# rhome_3.net
KiCad netlist of a schematic drawn in EAGLE
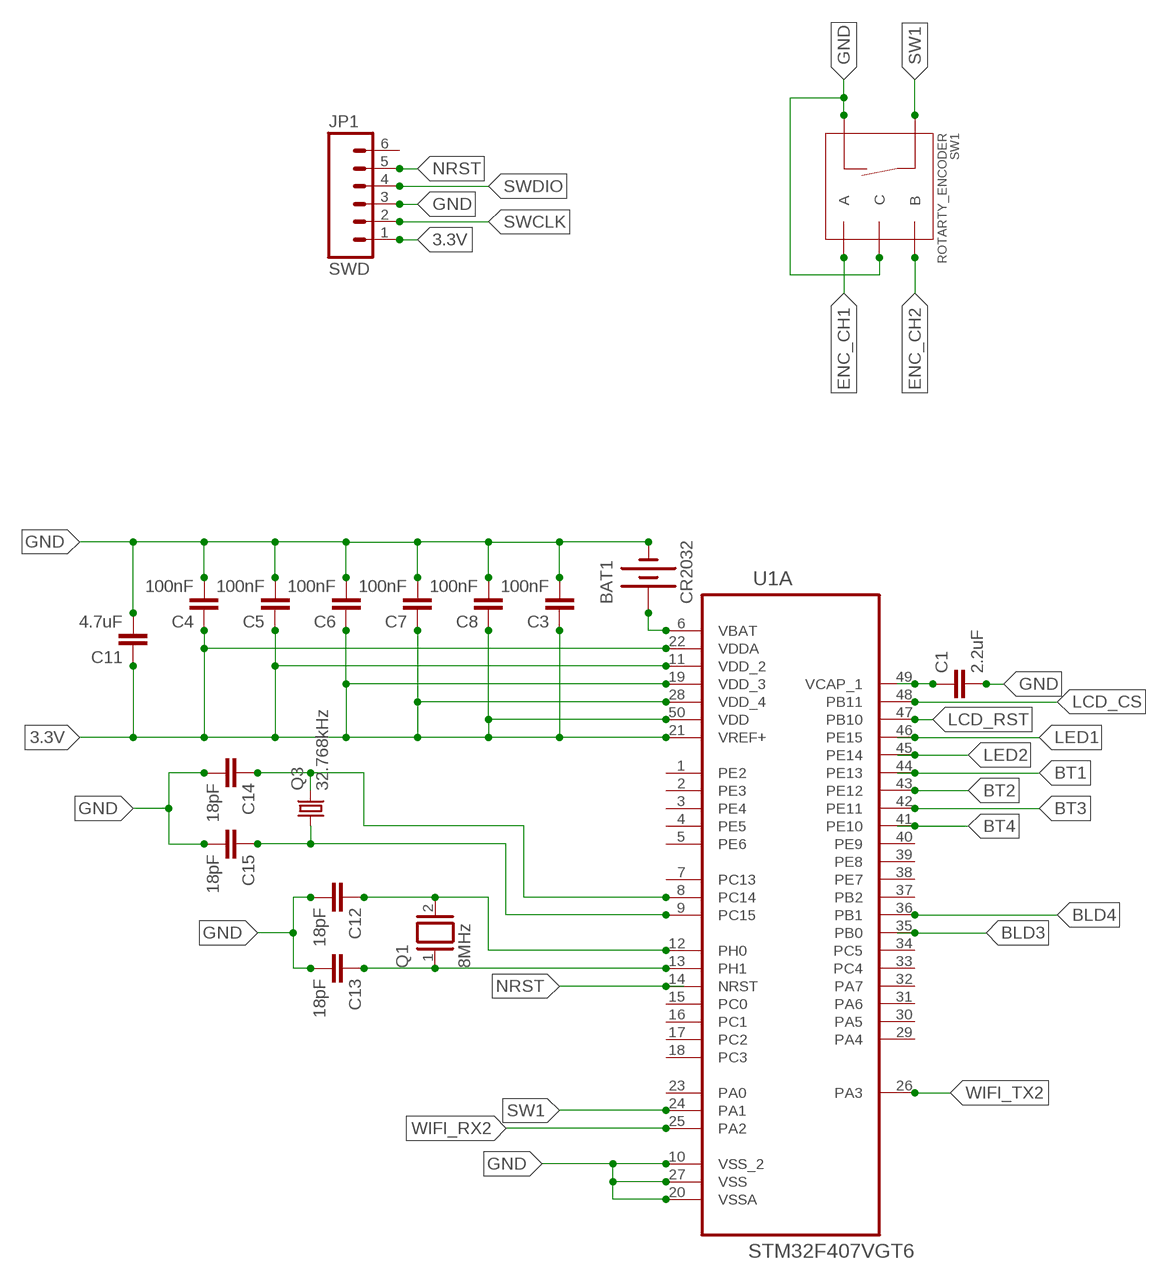
[diagram p0: schematic, sheet 1, part 1 of 2]
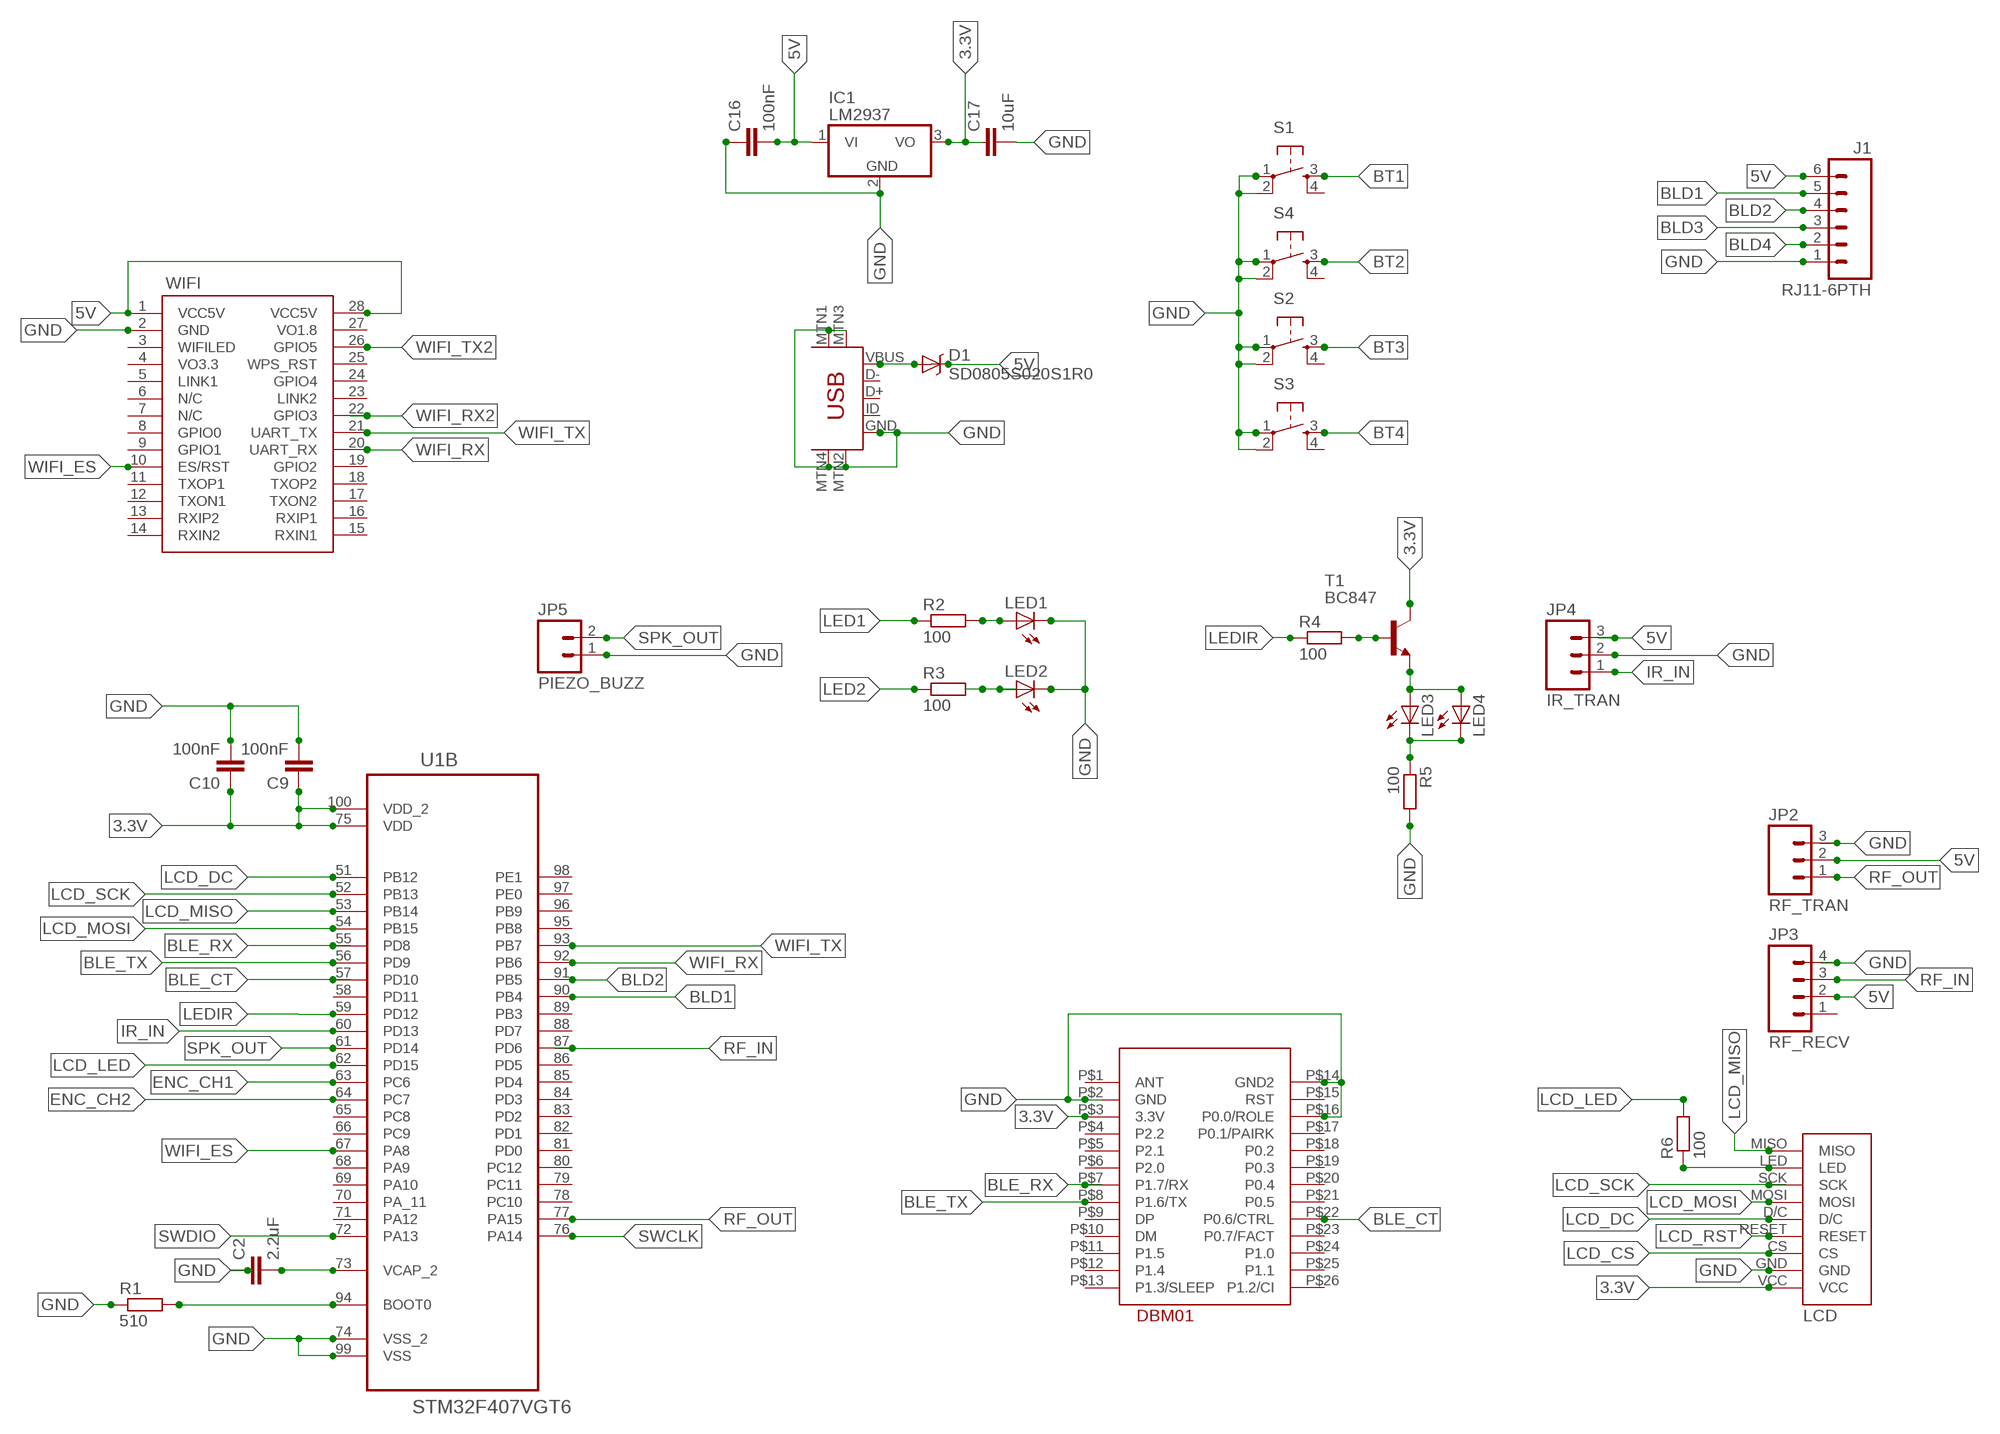
[diagram p1: schematic, sheet 1, part 2 of 2]

(export (version "E")
  (design (tool "Eeschema 10.0.6"))
  (components
    (comp (ref "BAT1")
      (value "CR2032")
      (footprint "eagle-import:BATTCON_20MM")
      (libsource (lib "eagle-import") (part "BATTERY20SMD"))
    )
    (comp (ref "C1")
      (value "2.2uF")
      (footprint "eagle-import:0805")
      (libsource (lib "eagle-import") (part "CAP0805"))
    )
    (comp (ref "C2")
      (value "2.2uF")
      (footprint "eagle-import:0805")
      (libsource (lib "eagle-import") (part "CAP0805"))
    )
    (comp (ref "C3")
      (value "100nF")
      (footprint "eagle-import:0805")
      (libsource (lib "eagle-import") (part "CAP0805"))
    )
    (comp (ref "C4")
      (value "100nF")
      (footprint "eagle-import:0805")
      (libsource (lib "eagle-import") (part "CAP0805"))
    )
    (comp (ref "C5")
      (value "100nF")
      (footprint "eagle-import:0805")
      (libsource (lib "eagle-import") (part "CAP0805"))
    )
    (comp (ref "C6")
      (value "100nF")
      (footprint "eagle-import:0805")
      (libsource (lib "eagle-import") (part "CAP0805"))
    )
    (comp (ref "C7")
      (value "100nF")
      (footprint "eagle-import:0805")
      (libsource (lib "eagle-import") (part "CAP0805"))
    )
    (comp (ref "C8")
      (value "100nF")
      (footprint "eagle-import:0805")
      (libsource (lib "eagle-import") (part "CAP0805"))
    )
    (comp (ref "C9")
      (value "100nF")
      (footprint "eagle-import:0805")
      (libsource (lib "eagle-import") (part "CAP0805"))
    )
    (comp (ref "C10")
      (value "100nF")
      (footprint "eagle-import:0805")
      (libsource (lib "eagle-import") (part "CAP0805"))
    )
    (comp (ref "C11")
      (value "4.7uF")
      (footprint "eagle-import:0805")
      (libsource (lib "eagle-import") (part "CAP0805"))
    )
    (comp (ref "C12")
      (value "18pF")
      (footprint "eagle-import:0805")
      (libsource (lib "eagle-import") (part "CAP0805"))
    )
    (comp (ref "C13")
      (value "18pF")
      (footprint "eagle-import:0805")
      (libsource (lib "eagle-import") (part "CAP0805"))
    )
    (comp (ref "C14")
      (value "18pF")
      (footprint "eagle-import:0805")
      (libsource (lib "eagle-import") (part "CAP0805"))
    )
    (comp (ref "C15")
      (value "18pF")
      (footprint "eagle-import:0805")
      (libsource (lib "eagle-import") (part "CAP0805"))
    )
    (comp (ref "C16")
      (value "100nF")
      (footprint "eagle-import:0805")
      (libsource (lib "eagle-import") (part "CAP0805"))
    )
    (comp (ref "C17")
      (value "10uF")
      (footprint "eagle-import:0805")
      (libsource (lib "eagle-import") (part "CAP0805"))
    )
    (comp (ref "D1")
      (value "SD0805S020S1R0")
      (footprint "eagle-import:SOD-323")
      (libsource (lib "eagle-import") (part "BAT20JFILM"))
    )
    (comp (ref "DBM01")
      (value "DBM01")
      (footprint "eagle-import:SMD")
      (libsource (lib "eagle-import") (part "DBM01"))
    )
    (comp (ref "IC1")
      (value "LM2937")
      (footprint "eagle-import:TO263-3")
      (libsource (lib "eagle-import") (part "LM2937"))
    )
    (comp (ref "J1")
      (value "RJ11-6PTH")
      (footprint "eagle-import:RJ11-6")
      (libsource (lib "eagle-import") (part "RJ11-6PTH"))
    )
    (comp (ref "JP1")
      (value "SWD")
      (footprint "eagle-import:1X06")
      (libsource (lib "eagle-import") (part "M06SIP"))
    )
    (comp (ref "JP2")
      (value "RF_TRAN")
      (footprint "eagle-import:1X03")
      (libsource (lib "eagle-import") (part "M03PTH"))
    )
    (comp (ref "JP3")
      (value "RF_RECV")
      (footprint "eagle-import:1X04")
      (libsource (lib "eagle-import") (part "M04PTH"))
    )
    (comp (ref "JP4")
      (value "IR_TRAN")
      (footprint "eagle-import:1X03")
      (libsource (lib "eagle-import") (part "M03PTH"))
    )
    (comp (ref "JP5")
      (value "PIEZO_BUZZ")
      (footprint "eagle-import:1X02_LOCK")
      (libsource (lib "eagle-import") (part "M02LOCK"))
    )
    (comp (ref "LCD")
      (value "ILI9341_SPI_LCD")
      (footprint "eagle-import:LCD")
      (libsource (lib "eagle-import") (part "ILI9341_SPI_LCD"))
    )
    (comp (ref "LED1")
      (value "LED5MM")
      (footprint "eagle-import:LED5MM")
      (libsource (lib "eagle-import") (part "LED5MM"))
    )
    (comp (ref "LED2")
      (value "LED5MM")
      (footprint "eagle-import:LED5MM")
      (libsource (lib "eagle-import") (part "LED5MM"))
    )
    (comp (ref "LED3")
      (value "LED5MM")
      (footprint "eagle-import:LED5MM")
      (libsource (lib "eagle-import") (part "LED5MM"))
    )
    (comp (ref "LED4")
      (value "LED5MM")
      (footprint "eagle-import:LED5MM")
      (libsource (lib "eagle-import") (part "LED5MM"))
    )
    (comp (ref "Q1")
      (value "8MHz")
      (footprint "eagle-import:QS")
      (libsource (lib "eagle-import") (part "XTAL/S"))
    )
    (comp (ref "Q3")
      (value "32.768kHz")
      (footprint "eagle-import:MC-306")
      (fields (field (name "MPN") "MC-306 60.0KHZ  100PPM ,12.5PF"))
      (libsource (lib "eagle-import") (part "MC-306"))
    )
    (comp (ref "R1")
      (value "510")
      (footprint "eagle-import:R0805")
      (libsource (lib "eagle-import") (part "R-EU_R0805"))
    )
    (comp (ref "R2")
      (value "100")
      (footprint "eagle-import:R0805")
      (libsource (lib "eagle-import") (part "R-EU_R0805"))
    )
    (comp (ref "R3")
      (value "100")
      (footprint "eagle-import:R0805")
      (libsource (lib "eagle-import") (part "R-EU_R0805"))
    )
    (comp (ref "R4")
      (value "100")
      (footprint "eagle-import:R0805")
      (libsource (lib "eagle-import") (part "R-EU_R0805"))
    )
    (comp (ref "R5")
      (value "100")
      (footprint "eagle-import:R0805")
      (libsource (lib "eagle-import") (part "R-EU_R0805"))
    )
    (comp (ref "R6")
      (value "100")
      (footprint "eagle-import:R0805")
      (libsource (lib "eagle-import") (part "R-EU_R0805"))
    )
    (comp (ref "S1")
      (value "TAC_SWITCHPTH")
      (footprint "eagle-import:TACTILE-PTH")
      (libsource (lib "eagle-import") (part "TAC_SWITCHPTH"))
    )
    (comp (ref "S2")
      (value "TAC_SWITCHPTH")
      (footprint "eagle-import:TACTILE-PTH")
      (libsource (lib "eagle-import") (part "TAC_SWITCHPTH"))
    )
    (comp (ref "S3")
      (value "TAC_SWITCHPTH")
      (footprint "eagle-import:TACTILE-PTH")
      (libsource (lib "eagle-import") (part "TAC_SWITCHPTH"))
    )
    (comp (ref "S4")
      (value "TAC_SWITCHPTH")
      (footprint "eagle-import:TACTILE-PTH")
      (libsource (lib "eagle-import") (part "TAC_SWITCHPTH"))
    )
    (comp (ref "SW1")
      (value "ROTARTY_ENCODER")
      (footprint "eagle-import:ROTARY_ENC_PLAIN")
      (libsource (lib "eagle-import") (part "ROTARTY_ENCODER"))
    )
    (comp (ref "T1")
      (value "BC847")
      (footprint "eagle-import:SOT23")
      (libsource (lib "eagle-import") (part "BC847"))
    )
    (comp (ref "U$1")
      (value "USB-MINIB-5PIN")
      (footprint "eagle-import:USB-MINIB")
      (libsource (lib "eagle-import") (part "USB-MINIB-5PIN"))
    )
    (comp (ref "U1")
      (value "STM32F407VGT6")
      (footprint "eagle-import:QFP50P1600X1600X160-100N")
      (libsource (lib "eagle-import") (part "STM32F407VGT6"))
    )
    (comp (ref "WIFI")
      (value "HLK-RM04")
      (footprint "eagle-import:HLK-RM04")
      (libsource (lib "eagle-import") (part "HLK-RM04"))
    )
  )
  (nets
    (net (code "1") (name "3.3V") (class "Default")
      (node (ref "C10") (pin "1") (pinfunction "1_1") (pintype "passive"))
      (node (ref "C11") (pin "1") (pinfunction "1_1") (pintype "passive"))
      (node (ref "C17") (pin "1") (pinfunction "1_1") (pintype "passive"))
      (node (ref "C3") (pin "1") (pinfunction "1_1") (pintype "passive"))
      (node (ref "C4") (pin "1") (pinfunction "1_1") (pintype "passive"))
      (node (ref "C5") (pin "1") (pinfunction "1_1") (pintype "passive"))
      (node (ref "C6") (pin "1") (pinfunction "1_1") (pintype "passive"))
      (node (ref "C7") (pin "1") (pinfunction "1_1") (pintype "passive"))
      (node (ref "C8") (pin "1") (pinfunction "1_1") (pintype "passive"))
      (node (ref "C9") (pin "1") (pinfunction "1_1") (pintype "passive"))
      (node (ref "DBM01") (pin "P$3") (pinfunction "3.3V_P$3") (pintype "bidirectional"))
      (node (ref "IC1") (pin "3") (pinfunction "VO_3") (pintype "passive"))
      (node (ref "JP1") (pin "1") (pinfunction "1_1") (pintype "passive"))
      (node (ref "LCD") (pin "VCC") (pinfunction "VCC_VCC") (pintype "bidirectional"))
      (node (ref "T1") (pin "3") (pinfunction "C_3") (pintype "passive"))
      (node (ref "U1") (pin "100") (pinfunction "VDD_2_100") (pintype "power_in"))
      (node (ref "U1") (pin "11") (pinfunction "VDD_2_11") (pintype "power_in"))
      (node (ref "U1") (pin "19") (pinfunction "VDD_3_19") (pintype "power_in"))
      (node (ref "U1") (pin "21") (pinfunction "VREF+_21") (pintype "power_in"))
      (node (ref "U1") (pin "22") (pinfunction "VDDA_22") (pintype "power_in"))
      (node (ref "U1") (pin "28") (pinfunction "VDD_4_28") (pintype "power_in"))
      (node (ref "U1") (pin "50") (pinfunction "VDD_50") (pintype "power_in"))
      (node (ref "U1") (pin "75") (pinfunction "VDD_75") (pintype "power_in"))
    )
    (net (code "2") (name "5V") (class "Default")
      (node (ref "C16") (pin "2") (pinfunction "2_2") (pintype "passive"))
      (node (ref "D1") (pin "1") (pinfunction "C_1") (pintype "passive"))
      (node (ref "IC1") (pin "1") (pinfunction "VI_1") (pintype "input"))
      (node (ref "J1") (pin "6") (pinfunction "6_6") (pintype "passive"))
      (node (ref "JP2") (pin "2") (pinfunction "2_2") (pintype "passive"))
      (node (ref "JP3") (pin "2") (pinfunction "2_2") (pintype "passive"))
      (node (ref "JP4") (pin "3") (pinfunction "3_3") (pintype "passive"))
      (node (ref "WIFI") (pin "1") (pinfunction "VCC5V_1") (pintype "bidirectional"))
      (node (ref "WIFI") (pin "28") (pinfunction "VCC5V_28") (pintype "bidirectional"))
    )
    (net (code "3") (name "BLD1") (class "Default")
      (node (ref "J1") (pin "5") (pinfunction "5_5") (pintype "passive"))
      (node (ref "U1") (pin "90") (pinfunction "PB4_90") (pintype "bidirectional"))
    )
    (net (code "4") (name "BLD2") (class "Default")
      (node (ref "J1") (pin "4") (pinfunction "4_4") (pintype "passive"))
      (node (ref "U1") (pin "91") (pinfunction "PB5_91") (pintype "bidirectional"))
    )
    (net (code "5") (name "BLD3") (class "Default")
      (node (ref "J1") (pin "3") (pinfunction "3_3") (pintype "passive"))
      (node (ref "U1") (pin "35") (pinfunction "PB0_35") (pintype "bidirectional"))
    )
    (net (code "6") (name "BLD4") (class "Default")
      (node (ref "J1") (pin "2") (pinfunction "2_2") (pintype "passive"))
      (node (ref "U1") (pin "36") (pinfunction "PB1_36") (pintype "bidirectional"))
    )
    (net (code "7") (name "BLE_CT") (class "Default")
      (node (ref "DBM01") (pin "P$22") (pinfunction "P0.6/CTRL_P$22") (pintype "bidirectional"))
      (node (ref "U1") (pin "57") (pinfunction "PD10_57") (pintype "bidirectional"))
    )
    (net (code "8") (name "BLE_RX") (class "Default")
      (node (ref "DBM01") (pin "P$7") (pinfunction "P1.7/RX_P$7") (pintype "bidirectional"))
      (node (ref "U1") (pin "55") (pinfunction "PD8_55") (pintype "bidirectional"))
    )
    (net (code "9") (name "BLE_TX") (class "Default")
      (node (ref "DBM01") (pin "P$8") (pinfunction "P1.6/TX_P$8") (pintype "bidirectional"))
      (node (ref "U1") (pin "56") (pinfunction "PD9_56") (pintype "bidirectional"))
    )
    (net (code "10") (name "BT1") (class "Default")
      (node (ref "S1") (pin "3") (pinfunction "3_3") (pintype "passive"))
      (node (ref "U1") (pin "44") (pinfunction "PE13_44") (pintype "bidirectional"))
    )
    (net (code "11") (name "BT2") (class "Default")
      (node (ref "S4") (pin "3") (pinfunction "3_3") (pintype "passive"))
      (node (ref "U1") (pin "43") (pinfunction "PE12_43") (pintype "bidirectional"))
    )
    (net (code "12") (name "BT3") (class "Default")
      (node (ref "S2") (pin "3") (pinfunction "3_3") (pintype "passive"))
      (node (ref "U1") (pin "42") (pinfunction "PE11_42") (pintype "bidirectional"))
    )
    (net (code "13") (name "BT4") (class "Default")
      (node (ref "S3") (pin "3") (pinfunction "3_3") (pintype "passive"))
      (node (ref "U1") (pin "41") (pinfunction "PE10_41") (pintype "bidirectional"))
    )
    (net (code "14") (name "ENC_CH1") (class "Default")
      (node (ref "SW1") (pin "A") (pinfunction "A_A") (pintype "bidirectional"))
      (node (ref "U1") (pin "63") (pinfunction "PC6_63") (pintype "bidirectional"))
    )
    (net (code "15") (name "ENC_CH2") (class "Default")
      (node (ref "SW1") (pin "B") (pinfunction "B_B") (pintype "bidirectional"))
      (node (ref "U1") (pin "64") (pinfunction "PC7_64") (pintype "bidirectional"))
    )
    (net (code "16") (name "GND") (class "Default")
      (node (ref "BAT1") (pin "2") (pinfunction "-_2") (pintype "power_in"))
      (node (ref "C1") (pin "2") (pinfunction "2_2") (pintype "passive"))
      (node (ref "C10") (pin "2") (pinfunction "2_2") (pintype "passive"))
      (node (ref "C11") (pin "2") (pinfunction "2_2") (pintype "passive"))
      (node (ref "C12") (pin "2") (pinfunction "2_2") (pintype "passive"))
      (node (ref "C13") (pin "2") (pinfunction "2_2") (pintype "passive"))
      (node (ref "C14") (pin "2") (pinfunction "2_2") (pintype "passive"))
      (node (ref "C15") (pin "2") (pinfunction "2_2") (pintype "passive"))
      (node (ref "C16") (pin "1") (pinfunction "1_1") (pintype "passive"))
      (node (ref "C17") (pin "2") (pinfunction "2_2") (pintype "passive"))
      (node (ref "C2") (pin "1") (pinfunction "1_1") (pintype "passive"))
      (node (ref "C3") (pin "2") (pinfunction "2_2") (pintype "passive"))
      (node (ref "C4") (pin "2") (pinfunction "2_2") (pintype "passive"))
      (node (ref "C5") (pin "2") (pinfunction "2_2") (pintype "passive"))
      (node (ref "C6") (pin "2") (pinfunction "2_2") (pintype "passive"))
      (node (ref "C7") (pin "2") (pinfunction "2_2") (pintype "passive"))
      (node (ref "C8") (pin "2") (pinfunction "2_2") (pintype "passive"))
      (node (ref "C9") (pin "2") (pinfunction "2_2") (pintype "passive"))
      (node (ref "DBM01") (pin "P$14") (pinfunction "GND2_P$14") (pintype "bidirectional"))
      (node (ref "DBM01") (pin "P$16") (pinfunction "P0.0/ROLE_P$16") (pintype "bidirectional"))
      (node (ref "DBM01") (pin "P$2") (pinfunction "GND_P$2") (pintype "bidirectional"))
      (node (ref "IC1") (pin "2") (pinfunction "GND_2") (pintype "passive"))
      (node (ref "J1") (pin "1") (pinfunction "1_1") (pintype "passive"))
      (node (ref "JP1") (pin "3") (pinfunction "3_3") (pintype "passive"))
      (node (ref "JP2") (pin "3") (pinfunction "3_3") (pintype "passive"))
      (node (ref "JP3") (pin "4") (pinfunction "4_4") (pintype "passive"))
      (node (ref "JP4") (pin "2") (pinfunction "2_2") (pintype "passive"))
      (node (ref "JP5") (pin "1") (pinfunction "1_1") (pintype "passive"))
      (node (ref "LCD") (pin "GND") (pinfunction "GND_GND") (pintype "bidirectional"))
      (node (ref "LED1") (pin "K") (pinfunction "C_K") (pintype "passive"))
      (node (ref "LED2") (pin "K") (pinfunction "C_K") (pintype "passive"))
      (node (ref "R1") (pin "1") (pinfunction "1_1") (pintype "passive"))
      (node (ref "R5") (pin "2") (pinfunction "2_2") (pintype "passive"))
      (node (ref "S1") (pin "1") (pinfunction "1_1") (pintype "passive"))
      (node (ref "S1") (pin "2") (pinfunction "2_2") (pintype "passive"))
      (node (ref "S2") (pin "1") (pinfunction "1_1") (pintype "passive"))
      (node (ref "S2") (pin "2") (pinfunction "2_2") (pintype "passive"))
      (node (ref "S3") (pin "1") (pinfunction "1_1") (pintype "passive"))
      (node (ref "S3") (pin "2") (pinfunction "2_2") (pintype "passive"))
      (node (ref "S4") (pin "1") (pinfunction "1_1") (pintype "passive"))
      (node (ref "S4") (pin "2") (pinfunction "2_2") (pintype "passive"))
      (node (ref "SW1") (pin "C") (pinfunction "C_C") (pintype "bidirectional"))
      (node (ref "SW1") (pin "SW-") (pinfunction "SW-_SW-") (pintype "bidirectional"))
      (node (ref "U$1") (pin "GND") (pinfunction "GND_GND") (pintype "bidirectional"))
      (node (ref "U$1") (pin "MTN1") (pinfunction "MTN2_MTN1") (pintype "bidirectional"))
      (node (ref "U$1") (pin "MTN2") (pinfunction "MTN3_MTN2") (pintype "bidirectional"))
      (node (ref "U$1") (pin "MTN3") (pinfunction "MTN1_MTN3") (pintype "bidirectional"))
      (node (ref "U$1") (pin "MTN4") (pinfunction "MTN4_MTN4") (pintype "bidirectional"))
      (node (ref "U1") (pin "10") (pinfunction "VSS_2_10") (pintype "passive"))
      (node (ref "U1") (pin "20") (pinfunction "VSSA_20") (pintype "passive"))
      (node (ref "U1") (pin "27") (pinfunction "VSS_27") (pintype "passive"))
      (node (ref "U1") (pin "74") (pinfunction "VSS_2_74") (pintype "passive"))
      (node (ref "U1") (pin "99") (pinfunction "VSS_99") (pintype "passive"))
      (node (ref "WIFI") (pin "2") (pinfunction "GND_2") (pintype "bidirectional"))
    )
    (net (code "17") (name "IR_IN") (class "Default")
      (node (ref "JP4") (pin "1") (pinfunction "1_1") (pintype "passive"))
      (node (ref "U1") (pin "60") (pinfunction "PD13_60") (pintype "bidirectional"))
    )
    (net (code "18") (name "LCD_CS") (class "Default")
      (node (ref "LCD") (pin "CS") (pinfunction "CS_CS") (pintype "bidirectional"))
      (node (ref "U1") (pin "48") (pinfunction "PB11_48") (pintype "bidirectional"))
    )
    (net (code "19") (name "LCD_DC") (class "Default")
      (node (ref "LCD") (pin "D/C") (pinfunction "D/C_D/C") (pintype "bidirectional"))
      (node (ref "U1") (pin "51") (pinfunction "PB12_51") (pintype "bidirectional"))
    )
    (net (code "20") (name "LCD_LED") (class "Default")
      (node (ref "R6") (pin "2") (pinfunction "2_2") (pintype "passive"))
      (node (ref "U1") (pin "62") (pinfunction "PD15_62") (pintype "bidirectional"))
    )
    (net (code "21") (name "LCD_MISO") (class "Default")
      (node (ref "LCD") (pin "MISO") (pinfunction "MISO_MISO") (pintype "bidirectional"))
      (node (ref "U1") (pin "53") (pinfunction "PB14_53") (pintype "bidirectional"))
    )
    (net (code "22") (name "LCD_MOSI") (class "Default")
      (node (ref "LCD") (pin "MOSI") (pinfunction "MOSI_MOSI") (pintype "bidirectional"))
      (node (ref "U1") (pin "54") (pinfunction "PB15_54") (pintype "bidirectional"))
    )
    (net (code "23") (name "LCD_RST") (class "Default")
      (node (ref "LCD") (pin "RESET") (pinfunction "RESET_RESET") (pintype "bidirectional"))
      (node (ref "U1") (pin "47") (pinfunction "PB10_47") (pintype "bidirectional"))
    )
    (net (code "24") (name "LCD_SCK") (class "Default")
      (node (ref "LCD") (pin "SCK") (pinfunction "SCK_SCK") (pintype "bidirectional"))
      (node (ref "U1") (pin "52") (pinfunction "PB13_52") (pintype "bidirectional"))
    )
    (net (code "25") (name "LED1") (class "Default")
      (node (ref "R2") (pin "1") (pinfunction "1_1") (pintype "passive"))
      (node (ref "U1") (pin "46") (pinfunction "PE15_46") (pintype "bidirectional"))
    )
    (net (code "26") (name "LED2") (class "Default")
      (node (ref "R3") (pin "1") (pinfunction "1_1") (pintype "passive"))
      (node (ref "U1") (pin "45") (pinfunction "PE14_45") (pintype "bidirectional"))
    )
    (net (code "27") (name "LEDIR") (class "Default")
      (node (ref "R4") (pin "1") (pinfunction "1_1") (pintype "passive"))
      (node (ref "U1") (pin "59") (pinfunction "PD12_59") (pintype "bidirectional"))
    )
    (net (code "28") (name "NRST") (class "Default")
      (node (ref "JP1") (pin "5") (pinfunction "5_5") (pintype "passive"))
      (node (ref "U1") (pin "14") (pinfunction "NRST_14") (pintype "bidirectional"))
    )
    (net (code "29") (name "Net-(BAT1-+)") (class "Default")
      (node (ref "BAT1") (pin "1") (pinfunction "+_1") (pintype "power_in"))
      (node (ref "U1") (pin "6") (pinfunction "VBAT_6") (pintype "power_in"))
    )
    (net (code "30") (name "Net-(D1-A)") (class "Default")
      (node (ref "D1") (pin "2") (pinfunction "A_2") (pintype "passive"))
      (node (ref "U$1") (pin "VBUS") (pinfunction "VBUS_VBUS") (pintype "bidirectional"))
    )
    (net (code "31") (name "Net-(LCD-PadLED)") (class "Default")
      (node (ref "LCD") (pin "LED") (pinfunction "LED_LED") (pintype "bidirectional"))
      (node (ref "R6") (pin "1") (pinfunction "1_1") (pintype "passive"))
    )
    (net (code "32") (name "Net-(LED1-PadA)") (class "Default")
      (node (ref "LED1") (pin "A") (pinfunction "A_A") (pintype "passive"))
      (node (ref "R2") (pin "2") (pinfunction "2_2") (pintype "passive"))
    )
    (net (code "33") (name "Net-(LED2-PadA)") (class "Default")
      (node (ref "LED2") (pin "A") (pinfunction "A_A") (pintype "passive"))
      (node (ref "R3") (pin "2") (pinfunction "2_2") (pintype "passive"))
    )
    (net (code "34") (name "Net-(LED3-C)") (class "Default")
      (node (ref "LED3") (pin "K") (pinfunction "C_K") (pintype "passive"))
      (node (ref "LED4") (pin "K") (pinfunction "C_K") (pintype "passive"))
      (node (ref "R5") (pin "1") (pinfunction "1_1") (pintype "passive"))
    )
    (net (code "35") (name "Net-(Q3-2)") (class "Default")
      (node (ref "C14") (pin "1") (pinfunction "1_1") (pintype "passive"))
      (node (ref "Q3") (pin "4") (pinfunction "2_4") (pintype "passive"))
      (node (ref "U1") (pin "8") (pinfunction "PC14_8") (pintype "bidirectional"))
    )
    (net (code "36") (name "Net-(T1-B)") (class "Default")
      (node (ref "R4") (pin "2") (pinfunction "2_2") (pintype "passive"))
      (node (ref "T1") (pin "1") (pinfunction "B_1") (pintype "passive"))
    )
    (net (code "37") (name "Net-(T1-E)") (class "Default")
      (node (ref "LED3") (pin "A") (pinfunction "A_A") (pintype "passive"))
      (node (ref "LED4") (pin "A") (pinfunction "A_A") (pintype "passive"))
      (node (ref "T1") (pin "2") (pinfunction "E_2") (pintype "passive"))
    )
    (net (code "38") (name "Net-(U1A-PC15)") (class "Default")
      (node (ref "C15") (pin "1") (pinfunction "1_1") (pintype "passive"))
      (node (ref "Q3") (pin "1") (pinfunction "1_1") (pintype "passive"))
      (node (ref "U1") (pin "9") (pinfunction "PC15_9") (pintype "bidirectional"))
    )
    (net (code "39") (name "Net-(U1A-PH0)") (class "Default")
      (node (ref "C12") (pin "1") (pinfunction "1_1") (pintype "passive"))
      (node (ref "Q1") (pin "2") (pinfunction "2_2") (pintype "passive"))
      (node (ref "U1") (pin "12") (pinfunction "PH0_12") (pintype "bidirectional"))
    )
    (net (code "40") (name "Net-(U1A-PH1)") (class "Default")
      (node (ref "C13") (pin "1") (pinfunction "1_1") (pintype "passive"))
      (node (ref "Q1") (pin "1") (pinfunction "1_1") (pintype "passive"))
      (node (ref "U1") (pin "13") (pinfunction "PH1_13") (pintype "bidirectional"))
    )
    (net (code "41") (name "Net-(U1A-VCAP_1)") (class "Default")
      (node (ref "C1") (pin "1") (pinfunction "1_1") (pintype "passive"))
      (node (ref "U1") (pin "49") (pinfunction "VCAP_1_49") (pintype "power_in"))
    )
    (net (code "42") (name "Net-(U1B-BOOT0)") (class "Default")
      (node (ref "R1") (pin "2") (pinfunction "2_2") (pintype "passive"))
      (node (ref "U1") (pin "94") (pinfunction "BOOT0_94") (pintype "input"))
    )
    (net (code "43") (name "Net-(U1B-VCAP_2)") (class "Default")
      (node (ref "C2") (pin "2") (pinfunction "2_2") (pintype "passive"))
      (node (ref "U1") (pin "73") (pinfunction "VCAP_2_73") (pintype "power_in"))
    )
    (net (code "44") (name "RF_IN") (class "Default")
      (node (ref "JP3") (pin "3") (pinfunction "3_3") (pintype "passive"))
      (node (ref "U1") (pin "87") (pinfunction "PD6_87") (pintype "bidirectional"))
    )
    (net (code "45") (name "RF_OUT") (class "Default")
      (node (ref "JP2") (pin "1") (pinfunction "1_1") (pintype "passive"))
      (node (ref "U1") (pin "77") (pinfunction "PA15_77") (pintype "bidirectional"))
    )
    (net (code "46") (name "SPK_OUT") (class "Default")
      (node (ref "JP5") (pin "2") (pinfunction "2_2") (pintype "passive"))
      (node (ref "U1") (pin "61") (pinfunction "PD14_61") (pintype "bidirectional"))
    )
    (net (code "47") (name "SW1") (class "Default")
      (node (ref "SW1") (pin "SW+") (pinfunction "SW+_SW+") (pintype "bidirectional"))
      (node (ref "U1") (pin "24") (pinfunction "PA1_24") (pintype "bidirectional"))
    )
    (net (code "48") (name "SWCLK") (class "Default")
      (node (ref "JP1") (pin "2") (pinfunction "2_2") (pintype "passive"))
      (node (ref "U1") (pin "76") (pinfunction "PA14_76") (pintype "bidirectional"))
    )
    (net (code "49") (name "SWDIO") (class "Default")
      (node (ref "JP1") (pin "4") (pinfunction "4_4") (pintype "passive"))
      (node (ref "U1") (pin "72") (pinfunction "PA13_72") (pintype "bidirectional"))
    )
    (net (code "50") (name "WIFI_ES") (class "Default")
      (node (ref "U1") (pin "67") (pinfunction "PA8_67") (pintype "bidirectional"))
      (node (ref "WIFI") (pin "10") (pinfunction "ES/RST_10") (pintype "bidirectional"))
    )
    (net (code "51") (name "WIFI_RX") (class "Default")
      (node (ref "U1") (pin "92") (pinfunction "PB6_92") (pintype "bidirectional"))
      (node (ref "WIFI") (pin "20") (pinfunction "UART_RX_20") (pintype "bidirectional"))
    )
    (net (code "52") (name "WIFI_RX2") (class "Default")
      (node (ref "U1") (pin "25") (pinfunction "PA2_25") (pintype "bidirectional"))
      (node (ref "WIFI") (pin "22") (pinfunction "GPIO3_22") (pintype "bidirectional"))
    )
    (net (code "53") (name "WIFI_TX") (class "Default")
      (node (ref "U1") (pin "93") (pinfunction "PB7_93") (pintype "bidirectional"))
      (node (ref "WIFI") (pin "21") (pinfunction "UART_TX_21") (pintype "bidirectional"))
    )
    (net (code "54") (name "WIFI_TX2") (class "Default")
      (node (ref "U1") (pin "26") (pinfunction "PA3_26") (pintype "bidirectional"))
      (node (ref "WIFI") (pin "26") (pinfunction "GPIO5_26") (pintype "bidirectional"))
    )
    (net (code "55") (name "unconnected-(DBM01-ANT-PadP$1)") (class "Default")
      (node (ref "DBM01") (pin "P$1") (pinfunction "ANT_P$1") (pintype "bidirectional"))
    )
    (net (code "56") (name "unconnected-(DBM01-DM-PadP$10)") (class "Default")
      (node (ref "DBM01") (pin "P$10") (pinfunction "DM_P$10") (pintype "bidirectional"))
    )
    (net (code "57") (name "unconnected-(DBM01-DP-PadP$9)") (class "Default")
      (node (ref "DBM01") (pin "P$9") (pinfunction "DP_P$9") (pintype "bidirectional"))
    )
    (net (code "58") (name "unconnected-(DBM01-P0.1{slash}PAIRK-PadP$17)") (class "Default")
      (node (ref "DBM01") (pin "P$17") (pinfunction "P0.1/PAIRK_P$17") (pintype "bidirectional"))
    )
    (net (code "59") (name "unconnected-(DBM01-P0.2-PadP$18)") (class "Default")
      (node (ref "DBM01") (pin "P$18") (pinfunction "P0.2_P$18") (pintype "bidirectional"))
    )
    (net (code "60") (name "unconnected-(DBM01-P0.3-PadP$19)") (class "Default")
      (node (ref "DBM01") (pin "P$19") (pinfunction "P0.3_P$19") (pintype "bidirectional"))
    )
    (net (code "61") (name "unconnected-(DBM01-P0.4-PadP$20)") (class "Default")
      (node (ref "DBM01") (pin "P$20") (pinfunction "P0.4_P$20") (pintype "bidirectional"))
    )
    (net (code "62") (name "unconnected-(DBM01-P0.5-PadP$21)") (class "Default")
      (node (ref "DBM01") (pin "P$21") (pinfunction "P0.5_P$21") (pintype "bidirectional"))
    )
    (net (code "63") (name "unconnected-(DBM01-P0.7{slash}FACT-PadP$23)") (class "Default")
      (node (ref "DBM01") (pin "P$23") (pinfunction "P0.7/FACT_P$23") (pintype "bidirectional"))
    )
    (net (code "64") (name "unconnected-(DBM01-P1.0-PadP$24)") (class "Default")
      (node (ref "DBM01") (pin "P$24") (pinfunction "P1.0_P$24") (pintype "bidirectional"))
    )
    (net (code "65") (name "unconnected-(DBM01-P1.1-PadP$25)") (class "Default")
      (node (ref "DBM01") (pin "P$25") (pinfunction "P1.1_P$25") (pintype "bidirectional"))
    )
    (net (code "66") (name "unconnected-(DBM01-P1.2{slash}CI-PadP$26)") (class "Default")
      (node (ref "DBM01") (pin "P$26") (pinfunction "P1.2/CI_P$26") (pintype "bidirectional"))
    )
    (net (code "67") (name "unconnected-(DBM01-P1.3{slash}SLEEP-PadP$13)") (class "Default")
      (node (ref "DBM01") (pin "P$13") (pinfunction "P1.3/SLEEP_P$13") (pintype "bidirectional"))
    )
    (net (code "68") (name "unconnected-(DBM01-P1.4-PadP$12)") (class "Default")
      (node (ref "DBM01") (pin "P$12") (pinfunction "P1.4_P$12") (pintype "bidirectional"))
    )
    (net (code "69") (name "unconnected-(DBM01-P1.5-PadP$11)") (class "Default")
      (node (ref "DBM01") (pin "P$11") (pinfunction "P1.5_P$11") (pintype "bidirectional"))
    )
    (net (code "70") (name "unconnected-(DBM01-P2.0-PadP$6)") (class "Default")
      (node (ref "DBM01") (pin "P$6") (pinfunction "P2.0_P$6") (pintype "bidirectional"))
    )
    (net (code "71") (name "unconnected-(DBM01-P2.1-PadP$5)") (class "Default")
      (node (ref "DBM01") (pin "P$5") (pinfunction "P2.1_P$5") (pintype "bidirectional"))
    )
    (net (code "72") (name "unconnected-(DBM01-P2.2-PadP$4)") (class "Default")
      (node (ref "DBM01") (pin "P$4") (pinfunction "P2.2_P$4") (pintype "bidirectional"))
    )
    (net (code "73") (name "unconnected-(DBM01-RST-PadP$15)") (class "Default")
      (node (ref "DBM01") (pin "P$15") (pinfunction "RST_P$15") (pintype "bidirectional"))
    )
    (net (code "74") (name "unconnected-(JP1-Pad6)") (class "Default")
      (node (ref "JP1") (pin "6") (pinfunction "6_6") (pintype "passive"))
    )
    (net (code "75") (name "unconnected-(JP3-Pad1)") (class "Default")
      (node (ref "JP3") (pin "1") (pinfunction "1_1") (pintype "passive"))
    )
    (net (code "76") (name "unconnected-(S1-Pad4)") (class "Default")
      (node (ref "S1") (pin "4") (pinfunction "4_4") (pintype "passive"))
    )
    (net (code "77") (name "unconnected-(S2-Pad4)") (class "Default")
      (node (ref "S2") (pin "4") (pinfunction "4_4") (pintype "passive"))
    )
    (net (code "78") (name "unconnected-(S3-Pad4)") (class "Default")
      (node (ref "S3") (pin "4") (pinfunction "4_4") (pintype "passive"))
    )
    (net (code "79") (name "unconnected-(S4-Pad4)") (class "Default")
      (node (ref "S4") (pin "4") (pinfunction "4_4") (pintype "passive"))
    )
    (net (code "80") (name "unconnected-(U$1-PadD+)") (class "Default")
      (node (ref "U$1") (pin "D+") (pinfunction "D+_D+") (pintype "bidirectional"))
    )
    (net (code "81") (name "unconnected-(U$1-PadD-)") (class "Default")
      (node (ref "U$1") (pin "D-") (pinfunction "D-_D-") (pintype "bidirectional"))
    )
    (net (code "82") (name "unconnected-(U$1-PadID)") (class "Default")
      (node (ref "U$1") (pin "ID") (pinfunction "ID_ID") (pintype "bidirectional"))
    )
    (net (code "83") (name "unconnected-(U1A-PA0-Pad23)") (class "Default")
      (node (ref "U1") (pin "23") (pinfunction "PA0_23") (pintype "bidirectional"))
    )
    (net (code "84") (name "unconnected-(U1A-PA4-Pad29)") (class "Default")
      (node (ref "U1") (pin "29") (pinfunction "PA4_29") (pintype "bidirectional"))
    )
    (net (code "85") (name "unconnected-(U1A-PA5-Pad30)") (class "Default")
      (node (ref "U1") (pin "30") (pinfunction "PA5_30") (pintype "bidirectional"))
    )
    (net (code "86") (name "unconnected-(U1A-PA6-Pad31)") (class "Default")
      (node (ref "U1") (pin "31") (pinfunction "PA6_31") (pintype "bidirectional"))
    )
    (net (code "87") (name "unconnected-(U1A-PA7-Pad32)") (class "Default")
      (node (ref "U1") (pin "32") (pinfunction "PA7_32") (pintype "bidirectional"))
    )
    (net (code "88") (name "unconnected-(U1A-PB2-Pad37)") (class "Default")
      (node (ref "U1") (pin "37") (pinfunction "PB2_37") (pintype "bidirectional"))
    )
    (net (code "89") (name "unconnected-(U1A-PC0-Pad15)") (class "Default")
      (node (ref "U1") (pin "15") (pinfunction "PC0_15") (pintype "bidirectional"))
    )
    (net (code "90") (name "unconnected-(U1A-PC1-Pad16)") (class "Default")
      (node (ref "U1") (pin "16") (pinfunction "PC1_16") (pintype "bidirectional"))
    )
    (net (code "91") (name "unconnected-(U1A-PC2-Pad17)") (class "Default")
      (node (ref "U1") (pin "17") (pinfunction "PC2_17") (pintype "bidirectional"))
    )
    (net (code "92") (name "unconnected-(U1A-PC3-Pad18)") (class "Default")
      (node (ref "U1") (pin "18") (pinfunction "PC3_18") (pintype "bidirectional"))
    )
    (net (code "93") (name "unconnected-(U1A-PC4-Pad33)") (class "Default")
      (node (ref "U1") (pin "33") (pinfunction "PC4_33") (pintype "bidirectional"))
    )
    (net (code "94") (name "unconnected-(U1A-PC5-Pad34)") (class "Default")
      (node (ref "U1") (pin "34") (pinfunction "PC5_34") (pintype "bidirectional"))
    )
    (net (code "95") (name "unconnected-(U1A-PC13-Pad7)") (class "Default")
      (node (ref "U1") (pin "7") (pinfunction "PC13_7") (pintype "bidirectional"))
    )
    (net (code "96") (name "unconnected-(U1A-PE2-Pad1)") (class "Default")
      (node (ref "U1") (pin "1") (pinfunction "PE2_1") (pintype "bidirectional"))
    )
    (net (code "97") (name "unconnected-(U1A-PE3-Pad2)") (class "Default")
      (node (ref "U1") (pin "2") (pinfunction "PE3_2") (pintype "bidirectional"))
    )
    (net (code "98") (name "unconnected-(U1A-PE4-Pad3)") (class "Default")
      (node (ref "U1") (pin "3") (pinfunction "PE4_3") (pintype "bidirectional"))
    )
    (net (code "99") (name "unconnected-(U1A-PE5-Pad4)") (class "Default")
      (node (ref "U1") (pin "4") (pinfunction "PE5_4") (pintype "bidirectional"))
    )
    (net (code "100") (name "unconnected-(U1A-PE6-Pad5)") (class "Default")
      (node (ref "U1") (pin "5") (pinfunction "PE6_5") (pintype "bidirectional"))
    )
    (net (code "101") (name "unconnected-(U1A-PE7-Pad38)") (class "Default")
      (node (ref "U1") (pin "38") (pinfunction "PE7_38") (pintype "bidirectional"))
    )
    (net (code "102") (name "unconnected-(U1A-PE8-Pad39)") (class "Default")
      (node (ref "U1") (pin "39") (pinfunction "PE8_39") (pintype "bidirectional"))
    )
    (net (code "103") (name "unconnected-(U1A-PE9-Pad40)") (class "Default")
      (node (ref "U1") (pin "40") (pinfunction "PE9_40") (pintype "bidirectional"))
    )
    (net (code "104") (name "unconnected-(U1B-PA9-Pad68)") (class "Default")
      (node (ref "U1") (pin "68") (pinfunction "PA9_68") (pintype "bidirectional"))
    )
    (net (code "105") (name "unconnected-(U1B-PA10-Pad69)") (class "Default")
      (node (ref "U1") (pin "69") (pinfunction "PA10_69") (pintype "bidirectional"))
    )
    (net (code "106") (name "unconnected-(U1B-PA12-Pad71)") (class "Default")
      (node (ref "U1") (pin "71") (pinfunction "PA12_71") (pintype "bidirectional"))
    )
    (net (code "107") (name "unconnected-(U1B-PA_11-Pad70)") (class "Default")
      (node (ref "U1") (pin "70") (pinfunction "PA_11_70") (pintype "bidirectional"))
    )
    (net (code "108") (name "unconnected-(U1B-PB3-Pad89)") (class "Default")
      (node (ref "U1") (pin "89") (pinfunction "PB3_89") (pintype "bidirectional"))
    )
    (net (code "109") (name "unconnected-(U1B-PB8-Pad95)") (class "Default")
      (node (ref "U1") (pin "95") (pinfunction "PB8_95") (pintype "bidirectional"))
    )
    (net (code "110") (name "unconnected-(U1B-PB9-Pad96)") (class "Default")
      (node (ref "U1") (pin "96") (pinfunction "PB9_96") (pintype "bidirectional"))
    )
    (net (code "111") (name "unconnected-(U1B-PC8-Pad65)") (class "Default")
      (node (ref "U1") (pin "65") (pinfunction "PC8_65") (pintype "bidirectional"))
    )
    (net (code "112") (name "unconnected-(U1B-PC9-Pad66)") (class "Default")
      (node (ref "U1") (pin "66") (pinfunction "PC9_66") (pintype "bidirectional"))
    )
    (net (code "113") (name "unconnected-(U1B-PC10-Pad78)") (class "Default")
      (node (ref "U1") (pin "78") (pinfunction "PC10_78") (pintype "bidirectional"))
    )
    (net (code "114") (name "unconnected-(U1B-PC11-Pad79)") (class "Default")
      (node (ref "U1") (pin "79") (pinfunction "PC11_79") (pintype "bidirectional"))
    )
    (net (code "115") (name "unconnected-(U1B-PC12-Pad80)") (class "Default")
      (node (ref "U1") (pin "80") (pinfunction "PC12_80") (pintype "bidirectional"))
    )
    (net (code "116") (name "unconnected-(U1B-PD0-Pad81)") (class "Default")
      (node (ref "U1") (pin "81") (pinfunction "PD0_81") (pintype "bidirectional"))
    )
    (net (code "117") (name "unconnected-(U1B-PD1-Pad82)") (class "Default")
      (node (ref "U1") (pin "82") (pinfunction "PD1_82") (pintype "bidirectional"))
    )
    (net (code "118") (name "unconnected-(U1B-PD2-Pad83)") (class "Default")
      (node (ref "U1") (pin "83") (pinfunction "PD2_83") (pintype "bidirectional"))
    )
    (net (code "119") (name "unconnected-(U1B-PD3-Pad84)") (class "Default")
      (node (ref "U1") (pin "84") (pinfunction "PD3_84") (pintype "bidirectional"))
    )
    (net (code "120") (name "unconnected-(U1B-PD4-Pad85)") (class "Default")
      (node (ref "U1") (pin "85") (pinfunction "PD4_85") (pintype "bidirectional"))
    )
    (net (code "121") (name "unconnected-(U1B-PD5-Pad86)") (class "Default")
      (node (ref "U1") (pin "86") (pinfunction "PD5_86") (pintype "bidirectional"))
    )
    (net (code "122") (name "unconnected-(U1B-PD7-Pad88)") (class "Default")
      (node (ref "U1") (pin "88") (pinfunction "PD7_88") (pintype "bidirectional"))
    )
    (net (code "123") (name "unconnected-(U1B-PD11-Pad58)") (class "Default")
      (node (ref "U1") (pin "58") (pinfunction "PD11_58") (pintype "bidirectional"))
    )
    (net (code "124") (name "unconnected-(U1B-PE0-Pad97)") (class "Default")
      (node (ref "U1") (pin "97") (pinfunction "PE0_97") (pintype "bidirectional"))
    )
    (net (code "125") (name "unconnected-(U1B-PE1-Pad98)") (class "Default")
      (node (ref "U1") (pin "98") (pinfunction "PE1_98") (pintype "bidirectional"))
    )
    (net (code "126") (name "unconnected-(WIFI-GPIO0-Pad8)") (class "Default")
      (node (ref "WIFI") (pin "8") (pinfunction "GPIO0_8") (pintype "bidirectional"))
    )
    (net (code "127") (name "unconnected-(WIFI-GPIO1-Pad9)") (class "Default")
      (node (ref "WIFI") (pin "9") (pinfunction "GPIO1_9") (pintype "bidirectional"))
    )
    (net (code "128") (name "unconnected-(WIFI-GPIO2-Pad19)") (class "Default")
      (node (ref "WIFI") (pin "19") (pinfunction "GPIO2_19") (pintype "bidirectional"))
    )
    (net (code "129") (name "unconnected-(WIFI-GPIO4-Pad24)") (class "Default")
      (node (ref "WIFI") (pin "24") (pinfunction "GPIO4_24") (pintype "bidirectional"))
    )
    (net (code "130") (name "unconnected-(WIFI-LINK1-Pad5)") (class "Default")
      (node (ref "WIFI") (pin "5") (pinfunction "LINK1_5") (pintype "bidirectional"))
    )
    (net (code "131") (name "unconnected-(WIFI-LINK2-Pad23)") (class "Default")
      (node (ref "WIFI") (pin "23") (pinfunction "LINK2_23") (pintype "bidirectional"))
    )
    (net (code "132") (name "unconnected-(WIFI-N{slash}C-Pad6)") (class "Default")
      (node (ref "WIFI") (pin "6") (pinfunction "N/C_6") (pintype "bidirectional"))
    )
    (net (code "133") (name "unconnected-(WIFI-N{slash}C-Pad7)") (class "Default")
      (node (ref "WIFI") (pin "7") (pinfunction "N/C_7") (pintype "bidirectional"))
    )
    (net (code "134") (name "unconnected-(WIFI-RXIN1-Pad15)") (class "Default")
      (node (ref "WIFI") (pin "15") (pinfunction "RXIN1_15") (pintype "bidirectional"))
    )
    (net (code "135") (name "unconnected-(WIFI-RXIN2-Pad14)") (class "Default")
      (node (ref "WIFI") (pin "14") (pinfunction "RXIN2_14") (pintype "bidirectional"))
    )
    (net (code "136") (name "unconnected-(WIFI-RXIP1-Pad16)") (class "Default")
      (node (ref "WIFI") (pin "16") (pinfunction "RXIP1_16") (pintype "bidirectional"))
    )
    (net (code "137") (name "unconnected-(WIFI-RXIP2-Pad13)") (class "Default")
      (node (ref "WIFI") (pin "13") (pinfunction "RXIP2_13") (pintype "bidirectional"))
    )
    (net (code "138") (name "unconnected-(WIFI-TXON1-Pad12)") (class "Default")
      (node (ref "WIFI") (pin "12") (pinfunction "TXON1_12") (pintype "bidirectional"))
    )
    (net (code "139") (name "unconnected-(WIFI-TXON2-Pad17)") (class "Default")
      (node (ref "WIFI") (pin "17") (pinfunction "TXON2_17") (pintype "bidirectional"))
    )
    (net (code "140") (name "unconnected-(WIFI-TXOP1-Pad11)") (class "Default")
      (node (ref "WIFI") (pin "11") (pinfunction "TXOP1_11") (pintype "bidirectional"))
    )
    (net (code "141") (name "unconnected-(WIFI-TXOP2-Pad18)") (class "Default")
      (node (ref "WIFI") (pin "18") (pinfunction "TXOP2_18") (pintype "bidirectional"))
    )
    (net (code "142") (name "unconnected-(WIFI-VO1.8-Pad27)") (class "Default")
      (node (ref "WIFI") (pin "27") (pinfunction "VO1.8_27") (pintype "bidirectional"))
    )
    (net (code "143") (name "unconnected-(WIFI-VO3.3-Pad4)") (class "Default")
      (node (ref "WIFI") (pin "4") (pinfunction "VO3.3_4") (pintype "bidirectional"))
    )
    (net (code "144") (name "unconnected-(WIFI-WIFILED-Pad3)") (class "Default")
      (node (ref "WIFI") (pin "3") (pinfunction "WIFILED_3") (pintype "bidirectional"))
    )
    (net (code "145") (name "unconnected-(WIFI-WPS_RST-Pad25)") (class "Default")
      (node (ref "WIFI") (pin "25") (pinfunction "WPS_RST_25") (pintype "bidirectional"))
    )
  )
)
